# DAC.net
KiCad netlist of a schematic drawn in Altium Designer
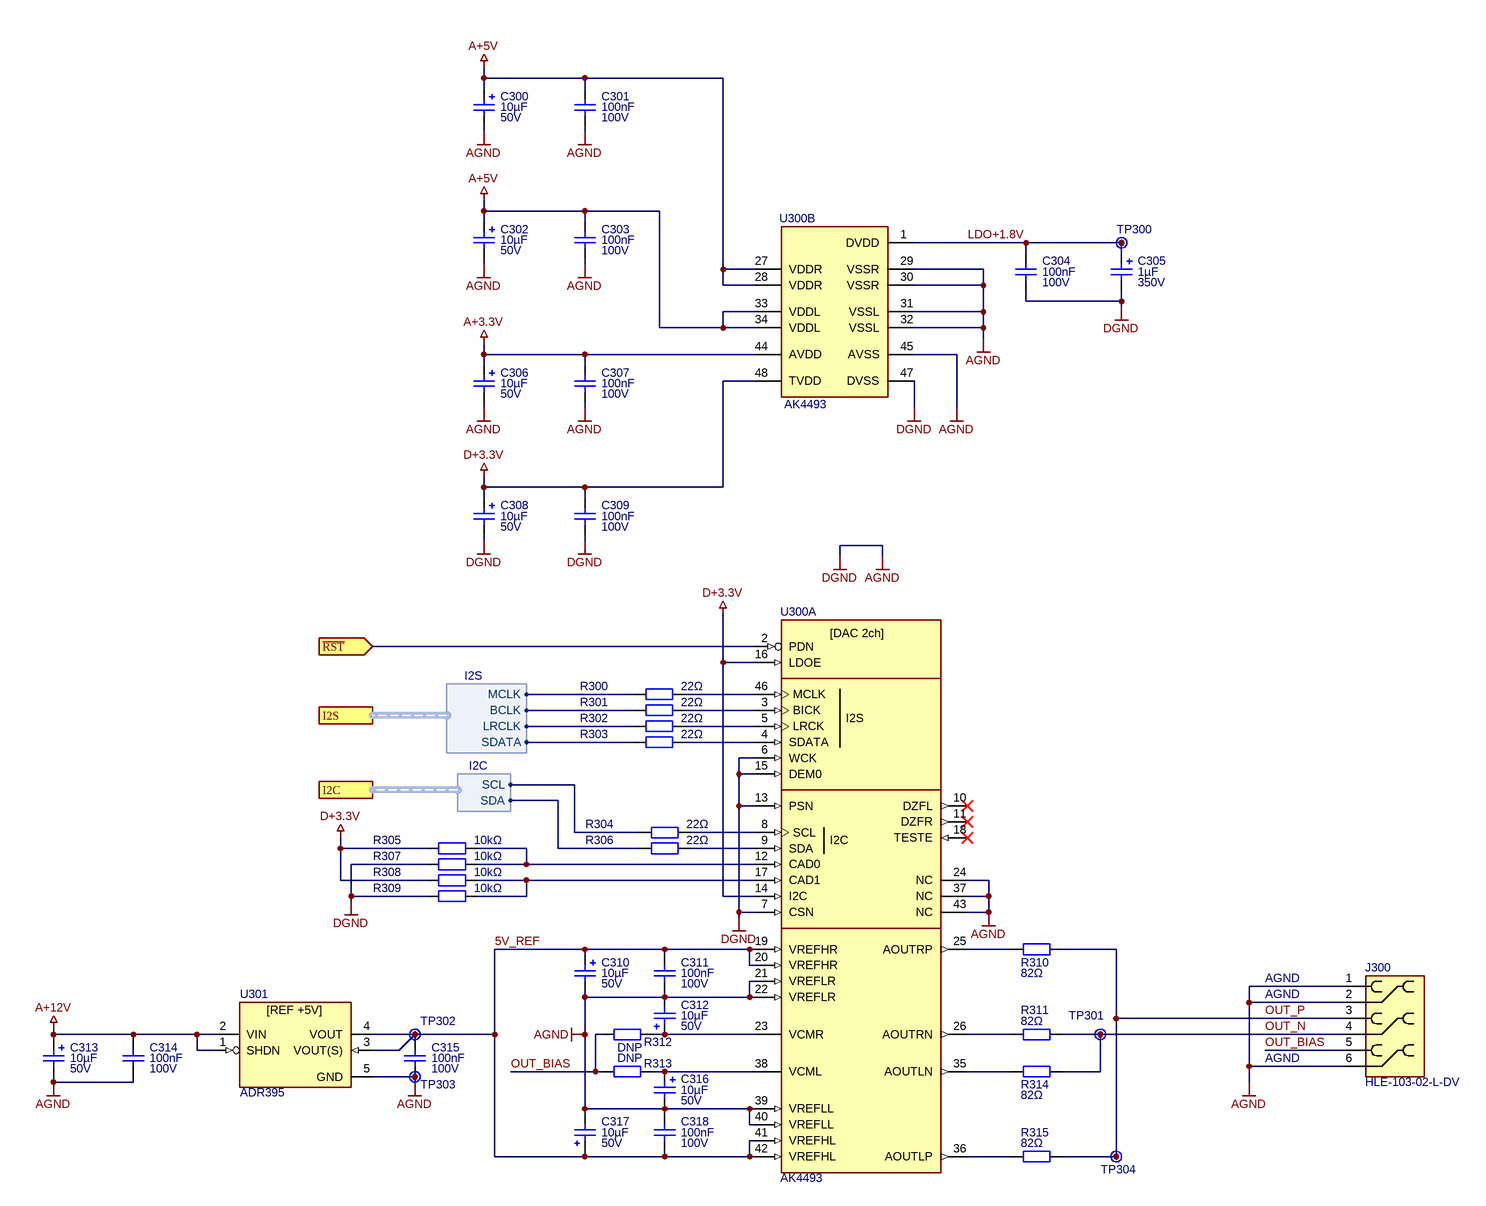
[diagram p0: DAC.SchDoc]

(export (version "E")
  (design (tool "Eeschema 10.0.6"))
  (components
    (comp (ref "C300")
      (value "10µF")
      (footprint "CAP-5-11.5-2")
      (description "Elektrolytic Capacitor")
      (fields (field (name "VOLTAGE") "50V") (field (name "MANUFACTURER PART NO.") "EEU-FR1H100"))
      (libsource (lib "Audio-Streamer") (part "Capacitor Electrolytic"))
    )
    (comp (ref "C301")
      (value "100nF")
      (footprint "CAP_WIMA_MKP4F")
      (description "Ceramic Capacitor")
      (fields (field (name "VOLTAGE") "100V") (field (name "MANUFACTURER PART NO.") "MKP2D031001F00KF00"))
      (libsource (lib "Audio-Streamer") (part "Capacitor Ceramic"))
    )
    (comp (ref "C302")
      (value "10µF")
      (footprint "CAP-5-11.5-2")
      (description "Elektrolytic Capacitor")
      (fields (field (name "VOLTAGE") "50V") (field (name "MANUFACTURER PART NO.") "EEU-FR1H100"))
      (libsource (lib "Audio-Streamer") (part "Capacitor Electrolytic"))
    )
    (comp (ref "C303")
      (value "100nF")
      (footprint "CAP_WIMA_MKP4F")
      (description "Ceramic Capacitor")
      (fields (field (name "VOLTAGE") "100V") (field (name "MANUFACTURER PART NO.") "MKP2D031001F00KF00"))
      (libsource (lib "Audio-Streamer") (part "Capacitor Ceramic"))
    )
    (comp (ref "C304")
      (value "100nF")
      (footprint "CAP_WIMA_MKP4F")
      (description "Ceramic Capacitor")
      (fields (field (name "VOLTAGE") "100V") (field (name "MANUFACTURER PART NO.") "MKP2D031001F00KF00"))
      (libsource (lib "Audio-Streamer") (part "Capacitor Ceramic"))
    )
    (comp (ref "C305")
      (value "1µF")
      (footprint "CAP-6.3-11.2-2.5")
      (description "Elektrolytic Capacitor")
      (fields (field (name "VOLTAGE") "350V"))
      (libsource (lib "Audio-Streamer") (part "Capacitor Electrolytic"))
    )
    (comp (ref "C306")
      (value "10µF")
      (footprint "CAP-5-11.5-2")
      (description "Elektrolytic Capacitor")
      (fields (field (name "VOLTAGE") "50V") (field (name "MANUFACTURER PART NO.") "EEU-FR1H100"))
      (libsource (lib "Audio-Streamer") (part "Capacitor Electrolytic"))
    )
    (comp (ref "C307")
      (value "100nF")
      (footprint "CAP_WIMA_MKP4F")
      (description "Ceramic Capacitor")
      (fields (field (name "VOLTAGE") "100V") (field (name "MANUFACTURER PART NO.") "MKP2D031001F00KF00"))
      (libsource (lib "Audio-Streamer") (part "Capacitor Ceramic"))
    )
    (comp (ref "C308")
      (value "10µF")
      (footprint "CAP-5-11.5-2")
      (description "Elektrolytic Capacitor")
      (fields (field (name "VOLTAGE") "50V") (field (name "MANUFACTURER PART NO.") "EEU-FR1H100"))
      (libsource (lib "Audio-Streamer") (part "Capacitor Electrolytic"))
    )
    (comp (ref "C309")
      (value "100nF")
      (footprint "CAP_WIMA_MKP4F")
      (description "Ceramic Capacitor")
      (fields (field (name "VOLTAGE") "100V") (field (name "MANUFACTURER PART NO.") "MKP2D031001F00KF00"))
      (libsource (lib "Audio-Streamer") (part "Capacitor Ceramic"))
    )
    (comp (ref "C310")
      (value "10µF")
      (footprint "CAP-5-11.5-2")
      (description "Elektrolytic Capacitor")
      (fields (field (name "VOLTAGE") "50V") (field (name "MANUFACTURER PART NO.") "EEU-FR1H100"))
      (libsource (lib "Audio-Streamer") (part "Capacitor Electrolytic"))
    )
    (comp (ref "C311")
      (value "100nF")
      (footprint "CAP_WIMA_MKP4F")
      (description "Ceramic Capacitor")
      (fields (field (name "VOLTAGE") "100V") (field (name "MANUFACTURER PART NO.") "MKP2D031001F00KF00"))
      (libsource (lib "Audio-Streamer") (part "Capacitor Ceramic"))
    )
    (comp (ref "C312")
      (value "10µF")
      (footprint "CAP-5-11.5-2")
      (description "Elektrolytic Capacitor")
      (fields (field (name "VOLTAGE") "50V") (field (name "MANUFACTURER PART NO.") "EEU-FR1H100"))
      (libsource (lib "Audio-Streamer") (part "Capacitor Electrolytic"))
    )
    (comp (ref "C313")
      (value "10µF")
      (footprint "CAP-5-11.5-2")
      (description "Elektrolytic Capacitor")
      (fields (field (name "VOLTAGE") "50V") (field (name "MANUFACTURER PART NO.") "EEU-FR1H100"))
      (libsource (lib "Audio-Streamer") (part "Capacitor Electrolytic"))
    )
    (comp (ref "C314")
      (value "100nF")
      (footprint "CAP_WIMA_MKP4F")
      (description "Ceramic Capacitor")
      (fields (field (name "VOLTAGE") "100V") (field (name "MANUFACTURER PART NO.") "MKP2D031001F00KF00"))
      (libsource (lib "Audio-Streamer") (part "Capacitor Ceramic"))
    )
    (comp (ref "C315")
      (value "100nF")
      (footprint "CAP_WIMA_MKP4F")
      (description "Ceramic Capacitor")
      (fields (field (name "VOLTAGE") "100V") (field (name "MANUFACTURER PART NO.") "MKP2D031001F00KF00"))
      (libsource (lib "Audio-Streamer") (part "Capacitor Ceramic"))
    )
    (comp (ref "C316")
      (value "10µF")
      (footprint "CAP-5-11.5-2")
      (description "Elektrolytic Capacitor")
      (fields (field (name "VOLTAGE") "50V") (field (name "MANUFACTURER PART NO.") "EEU-FR1H100"))
      (libsource (lib "Audio-Streamer") (part "Capacitor Electrolytic"))
    )
    (comp (ref "C317")
      (value "10µF")
      (footprint "CAP-5-11.5-2")
      (description "Elektrolytic Capacitor")
      (fields (field (name "VOLTAGE") "50V") (field (name "MANUFACTURER PART NO.") "EEU-FR1H100"))
      (libsource (lib "Audio-Streamer") (part "Capacitor Electrolytic"))
    )
    (comp (ref "C318")
      (value "100nF")
      (footprint "CAP_WIMA_MKP4F")
      (description "Ceramic Capacitor")
      (fields (field (name "VOLTAGE") "100V") (field (name "MANUFACTURER PART NO.") "MKP2D031001F00KF00"))
      (libsource (lib "Audio-Streamer") (part "Capacitor Ceramic"))
    )
    (comp (ref "J300")
      (value "HLE-103-02-L-DV")
      (footprint "HLE-103-02-XXX-DV")
      (description "Receptacle 3x2P")
      (libsource (lib "Audio-Streamer") (part "Receptacle 3x2P"))
    )
    (comp (ref "R300")
      (value "22Ω")
      (footprint "SMD0603RES")
      (description "Resistor")
      (libsource (lib "Audio-Streamer") (part "Resistor"))
    )
    (comp (ref "R301")
      (value "22Ω")
      (footprint "SMD0603RES")
      (description "Resistor")
      (libsource (lib "Audio-Streamer") (part "Resistor"))
    )
    (comp (ref "R302")
      (value "22Ω")
      (footprint "SMD0603RES")
      (description "Resistor")
      (libsource (lib "Audio-Streamer") (part "Resistor"))
    )
    (comp (ref "R303")
      (value "22Ω")
      (footprint "SMD0603RES")
      (description "Resistor")
      (libsource (lib "Audio-Streamer") (part "Resistor"))
    )
    (comp (ref "R304")
      (value "22Ω")
      (footprint "SMD0603RES")
      (description "Resistor")
      (libsource (lib "Audio-Streamer") (part "Resistor"))
    )
    (comp (ref "R305")
      (value "10kΩ")
      (footprint "SMD0603RES")
      (description "Resistor")
      (libsource (lib "Audio-Streamer") (part "Resistor"))
    )
    (comp (ref "R306")
      (value "22Ω")
      (footprint "SMD0603RES")
      (description "Resistor")
      (libsource (lib "Audio-Streamer") (part "Resistor"))
    )
    (comp (ref "R307")
      (value "10kΩ")
      (footprint "SMD0603RES")
      (description "Resistor")
      (libsource (lib "Audio-Streamer") (part "Resistor"))
    )
    (comp (ref "R308")
      (value "10kΩ")
      (footprint "SMD0603RES")
      (description "Resistor")
      (libsource (lib "Audio-Streamer") (part "Resistor"))
    )
    (comp (ref "R309")
      (value "10kΩ")
      (footprint "SMD0603RES")
      (description "Resistor")
      (libsource (lib "Audio-Streamer") (part "Resistor"))
    )
    (comp (ref "R310")
      (value "82Ω")
      (footprint "SMD0603RES")
      (description "Resistor Thin Film")
      (fields (field (name "MANUFACTURER PART NO.") "TNPW060322R0BEEA"))
      (libsource (lib "Audio-Streamer") (part "Resistor"))
    )
    (comp (ref "R311")
      (value "82Ω")
      (footprint "SMD0603RES")
      (description "Resistor Thin Film")
      (fields (field (name "MANUFACTURER PART NO.") "TNPW060322R0BEEA"))
      (libsource (lib "Audio-Streamer") (part "Resistor"))
    )
    (comp (ref "R312")
      (value "DNP")
      (footprint "SMD0603RES")
      (description "Resistor")
      (libsource (lib "Audio-Streamer") (part "Resistor"))
    )
    (comp (ref "R313")
      (value "DNP")
      (footprint "SMD0603RES")
      (description "Resistor")
      (libsource (lib "Audio-Streamer") (part "Resistor"))
    )
    (comp (ref "R314")
      (value "82Ω")
      (footprint "SMD0603RES")
      (description "Resistor Thin Film")
      (fields (field (name "MANUFACTURER PART NO.") "TNPW060322R0BEEA"))
      (libsource (lib "Audio-Streamer") (part "Resistor"))
    )
    (comp (ref "R315")
      (value "82Ω")
      (footprint "SMD0603RES")
      (description "Resistor Thin Film")
      (fields (field (name "MANUFACTURER PART NO.") "TNPW060322R0BEEA"))
      (libsource (lib "Audio-Streamer") (part "Resistor"))
    )
    (comp (ref "TP300")
      (value "Testpoint")
      (footprint "TP")
      (libsource (lib "Audio-Streamer") (part "Testpoint"))
    )
    (comp (ref "TP301")
      (value "Testpoint")
      (footprint "TP")
      (libsource (lib "Audio-Streamer") (part "Testpoint"))
    )
    (comp (ref "TP302")
      (value "Testpoint")
      (footprint "TP")
      (libsource (lib "Audio-Streamer") (part "Testpoint"))
    )
    (comp (ref "TP303")
      (value "Testpoint")
      (footprint "TP")
      (libsource (lib "Audio-Streamer") (part "Testpoint"))
    )
    (comp (ref "TP304")
      (value "Testpoint")
      (footprint "TP")
      (libsource (lib "Audio-Streamer") (part "Testpoint"))
    )
    (comp (ref "U300")
      (value "AK4493")
      (footprint "LQFP48")
      (description "32-Bit 2ch Audio DAC")
      (fields (field (name "MANUFACTURER PART NO.") "AK4493EQ"))
      (libsource (lib "Audio-Streamer") (part "AK4493"))
    )
    (comp (ref "U301")
      (value "ADR395")
      (footprint "SOT-23-5")
      (fields (field (name "MANUFACTURER PART NO.") "ADR395BUJZ-REEL7"))
      (libsource (lib "Audio-Streamer") (part "ADR395"))
    )
  )
  (nets
    (net (code "3") (name "/5V_REF") (class "Default")
      (node (ref "C310") (pin "P") (pinfunction "P_P") (pintype "passive"))
      (node (ref "C311") (pin "2") (pinfunction "q_2") (pintype "passive"))
      (node (ref "C315") (pin "2") (pinfunction "q_2") (pintype "passive"))
      (node (ref "C317") (pin "P") (pinfunction "P_P") (pintype "passive"))
      (node (ref "C318") (pin "1") (pinfunction "1_1") (pintype "passive"))
      (node (ref "TP302") (pin "1") (pinfunction "1_1") (pintype "passive"))
      (node (ref "U300") (pin "19") (pinfunction "VREFHR_19") (pintype "input"))
      (node (ref "U300") (pin "20") (pinfunction "VREFHR_20") (pintype "input"))
      (node (ref "U300") (pin "41") (pinfunction "VREFHL_41") (pintype "input"))
      (node (ref "U300") (pin "42") (pinfunction "VREFHL_42") (pintype "input"))
      (node (ref "U301") (pin "3") (pinfunction "VOUT(S)_3") (pintype "input"))
      (node (ref "U301") (pin "4") (pinfunction "VOUT_4") (pintype "power_in"))
    )
    (net (code "4") (name "/BCLK") (class "Default")
      (node (ref "R301") (pin "2") (pinfunction "2_2") (pintype "passive"))
    )
    (net (code "5") (name "/LDO+1.8V") (class "Default")
      (node (ref "C304") (pin "2") (pinfunction "q_2") (pintype "passive"))
      (node (ref "C305") (pin "P") (pinfunction "P_P") (pintype "passive"))
      (node (ref "TP300") (pin "1") (pinfunction "1_1") (pintype "passive"))
      (node (ref "U300") (pin "1") (pinfunction "DVDD_1") (pintype "power_in"))
    )
    (net (code "6") (name "/LRCLK") (class "Default")
      (node (ref "R302") (pin "2") (pinfunction "2_2") (pintype "passive"))
    )
    (net (code "7") (name "/MCLK") (class "Default")
      (node (ref "R300") (pin "2") (pinfunction "2_2") (pintype "passive"))
    )
    (net (code "8") (name "/OUT_BIAS") (class "Default")
      (node (ref "J300") (pin "5") (pinfunction "5_5") (pintype "passive"))
      (node (ref "R312") (pin "2") (pinfunction "2_2") (pintype "passive"))
      (node (ref "R313") (pin "2") (pinfunction "2_2") (pintype "passive"))
    )
    (net (code "9") (name "/OUT_N") (class "Default")
      (node (ref "J300") (pin "4") (pinfunction "4_4") (pintype "passive"))
      (node (ref "R311") (pin "1") (pinfunction "1_1") (pintype "passive"))
      (node (ref "R314") (pin "1") (pinfunction "1_1") (pintype "passive"))
      (node (ref "TP301") (pin "1") (pinfunction "1_1") (pintype "passive"))
    )
    (net (code "10") (name "/OUT_P") (class "Default")
      (node (ref "J300") (pin "3") (pinfunction "3_3") (pintype "passive"))
      (node (ref "R310") (pin "1") (pinfunction "1_1") (pintype "passive"))
      (node (ref "R315") (pin "1") (pinfunction "1_1") (pintype "passive"))
      (node (ref "TP304") (pin "1") (pinfunction "1_1") (pintype "passive"))
    )
    (net (code "11") (name "/SCL") (class "Default")
      (node (ref "R304") (pin "2") (pinfunction "2_2") (pintype "passive"))
    )
    (net (code "12") (name "/SDA") (class "Default")
      (node (ref "R306") (pin "2") (pinfunction "2_2") (pintype "passive"))
    )
    (net (code "13") (name "/SDATA") (class "Default")
      (node (ref "R303") (pin "2") (pinfunction "2_2") (pintype "passive"))
    )
    (net (code "16") (name "/~{RST}") (class "Default")
      (node (ref "U300") (pin "2") (pinfunction "PDN_2") (pintype "input"))
    )
    (net (code "17") (name "A+3.3V") (class "Default")
      (node (ref "C306") (pin "P") (pinfunction "P_P") (pintype "passive"))
      (node (ref "C307") (pin "2") (pinfunction "q_2") (pintype "passive"))
      (node (ref "U300") (pin "44") (pinfunction "AVDD_44") (pintype "power_in"))
    )
    (net (code "18") (name "A+5V") (class "Default")
      (node (ref "C300") (pin "P") (pinfunction "P_P") (pintype "passive"))
      (node (ref "C301") (pin "2") (pinfunction "q_2") (pintype "passive"))
      (node (ref "C302") (pin "P") (pinfunction "P_P") (pintype "passive"))
      (node (ref "C303") (pin "2") (pinfunction "q_2") (pintype "passive"))
      (node (ref "U300") (pin "27") (pinfunction "VDDR_27") (pintype "power_in"))
      (node (ref "U300") (pin "28") (pinfunction "VDDR_28") (pintype "power_in"))
      (node (ref "U300") (pin "33") (pinfunction "VDDL_33") (pintype "passive"))
      (node (ref "U300") (pin "34") (pinfunction "VDDL_34") (pintype "passive"))
    )
    (net (code "19") (name "A+12V") (class "Default")
      (node (ref "C313") (pin "P") (pinfunction "P_P") (pintype "passive"))
      (node (ref "C314") (pin "2") (pinfunction "q_2") (pintype "passive"))
      (node (ref "U301") (pin "1") (pinfunction "SHDN_1") (pintype "input"))
      (node (ref "U301") (pin "2") (pinfunction "VIN_2") (pintype "power_in"))
    )
    (net (code "20") (name "AGND") (class "Default")
      (node (ref "C300") (pin "M") (pinfunction "q_M") (pintype "passive"))
      (node (ref "C301") (pin "1") (pinfunction "1_1") (pintype "passive"))
      (node (ref "C302") (pin "M") (pinfunction "q_M") (pintype "passive"))
      (node (ref "C303") (pin "1") (pinfunction "1_1") (pintype "passive"))
      (node (ref "C304") (pin "1") (pinfunction "1_1") (pintype "passive"))
      (node (ref "C305") (pin "M") (pinfunction "q_M") (pintype "passive"))
      (node (ref "C306") (pin "M") (pinfunction "q_M") (pintype "passive"))
      (node (ref "C307") (pin "1") (pinfunction "1_1") (pintype "passive"))
      (node (ref "C308") (pin "M") (pinfunction "q_M") (pintype "passive"))
      (node (ref "C309") (pin "1") (pinfunction "1_1") (pintype "passive"))
      (node (ref "C310") (pin "M") (pinfunction "q_M") (pintype "passive"))
      (node (ref "C311") (pin "1") (pinfunction "1_1") (pintype "passive"))
      (node (ref "C312") (pin "M") (pinfunction "q_M") (pintype "passive"))
      (node (ref "C313") (pin "M") (pinfunction "q_M") (pintype "passive"))
      (node (ref "C314") (pin "1") (pinfunction "1_1") (pintype "passive"))
      (node (ref "C315") (pin "1") (pinfunction "1_1") (pintype "passive"))
      (node (ref "C316") (pin "M") (pinfunction "q_M") (pintype "passive"))
      (node (ref "C317") (pin "M") (pinfunction "q_M") (pintype "passive"))
      (node (ref "C318") (pin "2") (pinfunction "q_2") (pintype "passive"))
      (node (ref "J300") (pin "1") (pinfunction "1_1") (pintype "passive"))
      (node (ref "J300") (pin "2") (pinfunction "2_2") (pintype "passive"))
      (node (ref "J300") (pin "6") (pinfunction "6_6") (pintype "passive"))
      (node (ref "R307") (pin "2") (pinfunction "2_2") (pintype "passive"))
      (node (ref "R309") (pin "2") (pinfunction "2_2") (pintype "passive"))
      (node (ref "TP303") (pin "1") (pinfunction "1_1") (pintype "passive"))
      (node (ref "U300") (pin "13") (pinfunction "PSN_13") (pintype "input"))
      (node (ref "U300") (pin "15") (pinfunction "DEM0_15") (pintype "input"))
      (node (ref "U300") (pin "21") (pinfunction "VREFLR_21") (pintype "input"))
      (node (ref "U300") (pin "22") (pinfunction "VREFLR_22") (pintype "input"))
      (node (ref "U300") (pin "24") (pinfunction "NC_24") (pintype "passive"))
      (node (ref "U300") (pin "29") (pinfunction "VSSR_29") (pintype "power_in"))
      (node (ref "U300") (pin "30") (pinfunction "VSSR_30") (pintype "power_in"))
      (node (ref "U300") (pin "31") (pinfunction "VSSL_31") (pintype "power_in"))
      (node (ref "U300") (pin "32") (pinfunction "VSSL_32") (pintype "power_in"))
      (node (ref "U300") (pin "37") (pinfunction "NC_37") (pintype "passive"))
      (node (ref "U300") (pin "39") (pinfunction "VREFLL_39") (pintype "input"))
      (node (ref "U300") (pin "40") (pinfunction "VREFLL_40") (pintype "input"))
      (node (ref "U300") (pin "43") (pinfunction "NC_43") (pintype "passive"))
      (node (ref "U300") (pin "45") (pinfunction "AVSS_45") (pintype "power_in"))
      (node (ref "U300") (pin "47") (pinfunction "DVSS_47") (pintype "power_in"))
      (node (ref "U300") (pin "6") (pinfunction "WCK_6") (pintype "input"))
      (node (ref "U300") (pin "7") (pinfunction "CSN_7") (pintype "input"))
      (node (ref "U301") (pin "5") (pinfunction "GND_5") (pintype "power_in"))
    )
    (net (code "21") (name "D+3.3V") (class "Default")
      (node (ref "C308") (pin "P") (pinfunction "P_P") (pintype "passive"))
      (node (ref "C309") (pin "2") (pinfunction "q_2") (pintype "passive"))
      (node (ref "R305") (pin "2") (pinfunction "2_2") (pintype "passive"))
      (node (ref "R308") (pin "2") (pinfunction "2_2") (pintype "passive"))
      (node (ref "U300") (pin "14") (pinfunction "I2C_14") (pintype "input"))
      (node (ref "U300") (pin "16") (pinfunction "LDOE_16") (pintype "input"))
      (node (ref "U300") (pin "48") (pinfunction "TVDD_48") (pintype "power_in"))
    )
    (net (code "22") (name "Net-(U300A-AOUTLN)") (class "Default")
      (node (ref "R314") (pin "2") (pinfunction "2_2") (pintype "passive"))
      (node (ref "U300") (pin "35") (pinfunction "AOUTLN_35") (pintype "output"))
    )
    (net (code "23") (name "Net-(U300A-AOUTLP)") (class "Default")
      (node (ref "R315") (pin "2") (pinfunction "2_2") (pintype "passive"))
      (node (ref "U300") (pin "36") (pinfunction "AOUTLP_36") (pintype "output"))
    )
    (net (code "24") (name "Net-(U300A-AOUTRN)") (class "Default")
      (node (ref "R311") (pin "2") (pinfunction "2_2") (pintype "passive"))
      (node (ref "U300") (pin "26") (pinfunction "AOUTRN_26") (pintype "output"))
    )
    (net (code "25") (name "Net-(U300A-AOUTRP)") (class "Default")
      (node (ref "R310") (pin "2") (pinfunction "2_2") (pintype "passive"))
      (node (ref "U300") (pin "25") (pinfunction "AOUTRP_25") (pintype "output"))
    )
    (net (code "26") (name "Net-(U300A-BICK)") (class "Default")
      (node (ref "R301") (pin "1") (pinfunction "1_1") (pintype "passive"))
      (node (ref "U300") (pin "3") (pinfunction "BICK_3") (pintype "input"))
    )
    (net (code "27") (name "Net-(U300A-CAD0)") (class "Default")
      (node (ref "R305") (pin "1") (pinfunction "1_1") (pintype "passive"))
      (node (ref "R307") (pin "1") (pinfunction "1_1") (pintype "passive"))
      (node (ref "U300") (pin "12") (pinfunction "CAD0_12") (pintype "input"))
    )
    (net (code "28") (name "Net-(U300A-CAD1)") (class "Default")
      (node (ref "R308") (pin "1") (pinfunction "1_1") (pintype "passive"))
      (node (ref "R309") (pin "1") (pinfunction "1_1") (pintype "passive"))
      (node (ref "U300") (pin "17") (pinfunction "CAD1_17") (pintype "input"))
    )
    (net (code "29") (name "Net-(U300A-LRCK)") (class "Default")
      (node (ref "R302") (pin "1") (pinfunction "1_1") (pintype "passive"))
      (node (ref "U300") (pin "5") (pinfunction "LRCK_5") (pintype "input"))
    )
    (net (code "30") (name "Net-(U300A-MCLK)") (class "Default")
      (node (ref "R300") (pin "1") (pinfunction "1_1") (pintype "passive"))
      (node (ref "U300") (pin "46") (pinfunction "MCLK_46") (pintype "input"))
    )
    (net (code "31") (name "Net-(U300A-SCL)") (class "Default")
      (node (ref "R304") (pin "1") (pinfunction "1_1") (pintype "passive"))
      (node (ref "U300") (pin "8") (pinfunction "SCL_8") (pintype "input"))
    )
    (net (code "32") (name "Net-(U300A-SDA)") (class "Default")
      (node (ref "R306") (pin "1") (pinfunction "1_1") (pintype "passive"))
      (node (ref "U300") (pin "9") (pinfunction "SDA_9") (pintype "input"))
    )
    (net (code "33") (name "Net-(U300A-SDATA)") (class "Default")
      (node (ref "R303") (pin "1") (pinfunction "1_1") (pintype "passive"))
      (node (ref "U300") (pin "4") (pinfunction "SDATA_4") (pintype "input"))
    )
    (net (code "34") (name "Net-(U300A-VCML)") (class "Default")
      (node (ref "C316") (pin "P") (pinfunction "P_P") (pintype "passive"))
      (node (ref "R313") (pin "1") (pinfunction "1_1") (pintype "passive"))
      (node (ref "U300") (pin "38") (pinfunction "VCML_38") (pintype "power_in"))
    )
    (net (code "35") (name "Net-(U300A-VCMR)") (class "Default")
      (node (ref "C312") (pin "P") (pinfunction "P_P") (pintype "passive"))
      (node (ref "R312") (pin "1") (pinfunction "1_1") (pintype "passive"))
      (node (ref "U300") (pin "23") (pinfunction "VCMR_23") (pintype "power_in"))
    )
    (net (code "36") (name "unconnected-(U300A-DZFL-Pad10)") (class "Default")
      (node (ref "U300") (pin "10") (pinfunction "DZFL_10") (pintype "output+no_connect"))
    )
    (net (code "37") (name "unconnected-(U300A-DZFR-Pad11)") (class "Default")
      (node (ref "U300") (pin "11") (pinfunction "DZFR_11") (pintype "output+no_connect"))
    )
    (net (code "38") (name "unconnected-(U300A-TESTE-Pad18)") (class "Default")
      (node (ref "U300") (pin "18") (pinfunction "TESTE_18") (pintype "input+no_connect"))
    )
  )
)
